# ardumsx.net
KiCad netlist of a schematic drawn in EAGLE
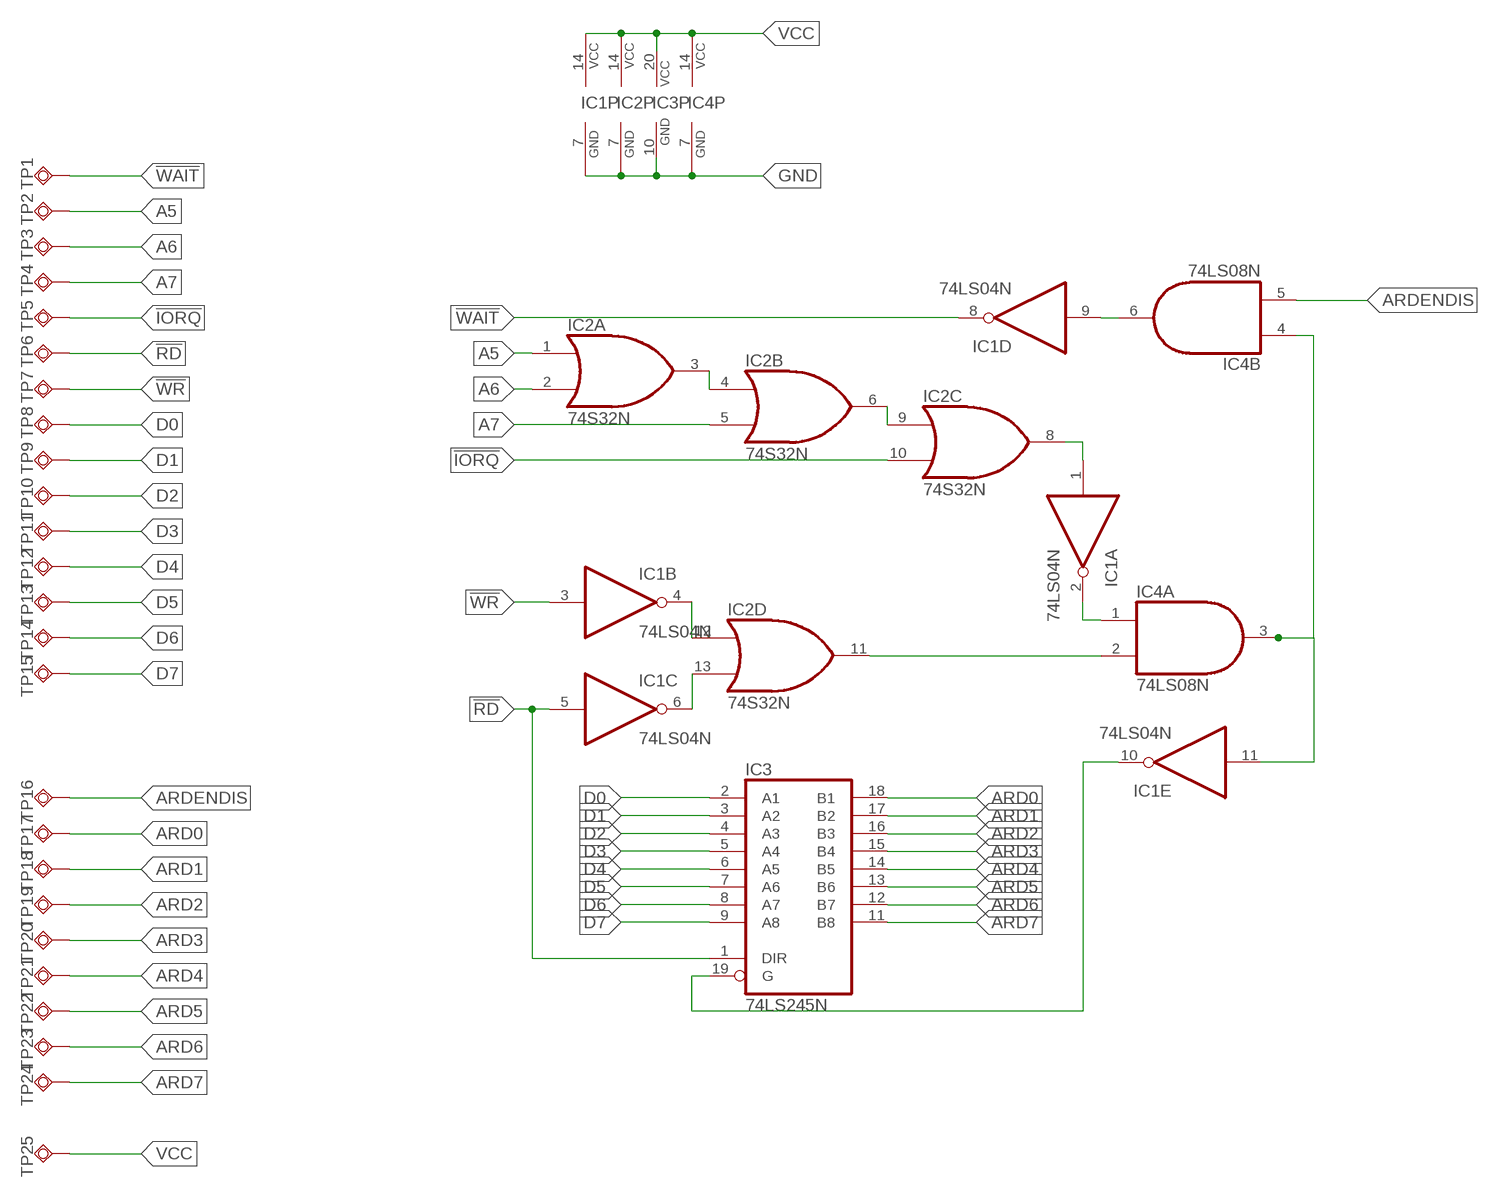
[diagram p0: schematic, sheet 1]

(export (version "E")
  (design (tool "Eeschema 10.0.6"))
  (components
    (comp (ref "IC1")
      (value "74LS04N")
      (footprint "eagle-import:DIL14")
      (libsource (lib "eagle-import") (part "7404NLS"))
    )
    (comp (ref "IC2")
      (value "74S32N")
      (footprint "eagle-import:DIL14")
      (libsource (lib "eagle-import") (part "7432NS"))
    )
    (comp (ref "IC3")
      (value "74LS245N")
      (footprint "eagle-import:DIL20")
      (libsource (lib "eagle-import") (part "74245NLS"))
    )
    (comp (ref "IC4")
      (value "74LS08N")
      (footprint "eagle-import:DIL14")
      (libsource (lib "eagle-import") (part "7408NLS"))
    )
    (comp (ref "TP1")
      (value "TPSQTP17R")
      (footprint "eagle-import:TP17R")
      (libsource (lib "eagle-import") (part "TPSQTP17R"))
    )
    (comp (ref "TP2")
      (value "TPSQTP17R")
      (footprint "eagle-import:TP17R")
      (libsource (lib "eagle-import") (part "TPSQTP17R"))
    )
    (comp (ref "TP3")
      (value "TPSQTP17R")
      (footprint "eagle-import:TP17R")
      (libsource (lib "eagle-import") (part "TPSQTP17R"))
    )
    (comp (ref "TP4")
      (value "TPSQTP17R")
      (footprint "eagle-import:TP17R")
      (libsource (lib "eagle-import") (part "TPSQTP17R"))
    )
    (comp (ref "TP5")
      (value "TPSQTP17R")
      (footprint "eagle-import:TP17R")
      (libsource (lib "eagle-import") (part "TPSQTP17R"))
    )
    (comp (ref "TP6")
      (value "TPSQTP17R")
      (footprint "eagle-import:TP17R")
      (libsource (lib "eagle-import") (part "TPSQTP17R"))
    )
    (comp (ref "TP7")
      (value "TPSQTP17R")
      (footprint "eagle-import:TP17R")
      (libsource (lib "eagle-import") (part "TPSQTP17R"))
    )
    (comp (ref "TP8")
      (value "TPSQTP17R")
      (footprint "eagle-import:TP17R")
      (libsource (lib "eagle-import") (part "TPSQTP17R"))
    )
    (comp (ref "TP9")
      (value "TPSQTP17R")
      (footprint "eagle-import:TP17R")
      (libsource (lib "eagle-import") (part "TPSQTP17R"))
    )
    (comp (ref "TP10")
      (value "TPSQTP17R")
      (footprint "eagle-import:TP17R")
      (libsource (lib "eagle-import") (part "TPSQTP17R"))
    )
    (comp (ref "TP11")
      (value "TPSQTP17R")
      (footprint "eagle-import:TP17R")
      (libsource (lib "eagle-import") (part "TPSQTP17R"))
    )
    (comp (ref "TP12")
      (value "TPSQTP17R")
      (footprint "eagle-import:TP17R")
      (libsource (lib "eagle-import") (part "TPSQTP17R"))
    )
    (comp (ref "TP13")
      (value "TPSQTP17R")
      (footprint "eagle-import:TP17R")
      (libsource (lib "eagle-import") (part "TPSQTP17R"))
    )
    (comp (ref "TP14")
      (value "TPSQTP17R")
      (footprint "eagle-import:TP17R")
      (libsource (lib "eagle-import") (part "TPSQTP17R"))
    )
    (comp (ref "TP15")
      (value "TPSQTP17R")
      (footprint "eagle-import:TP17R")
      (libsource (lib "eagle-import") (part "TPSQTP17R"))
    )
    (comp (ref "TP16")
      (value "TPSQTP17R")
      (footprint "eagle-import:TP17R")
      (libsource (lib "eagle-import") (part "TPSQTP17R"))
    )
    (comp (ref "TP17")
      (value "TPSQTP17R")
      (footprint "eagle-import:TP17R")
      (libsource (lib "eagle-import") (part "TPSQTP17R"))
    )
    (comp (ref "TP18")
      (value "TPSQTP17R")
      (footprint "eagle-import:TP17R")
      (libsource (lib "eagle-import") (part "TPSQTP17R"))
    )
    (comp (ref "TP19")
      (value "TPSQTP17R")
      (footprint "eagle-import:TP17R")
      (libsource (lib "eagle-import") (part "TPSQTP17R"))
    )
    (comp (ref "TP20")
      (value "TPSQTP17R")
      (footprint "eagle-import:TP17R")
      (libsource (lib "eagle-import") (part "TPSQTP17R"))
    )
    (comp (ref "TP21")
      (value "TPSQTP17R")
      (footprint "eagle-import:TP17R")
      (libsource (lib "eagle-import") (part "TPSQTP17R"))
    )
    (comp (ref "TP22")
      (value "TPSQTP17R")
      (footprint "eagle-import:TP17R")
      (libsource (lib "eagle-import") (part "TPSQTP17R"))
    )
    (comp (ref "TP23")
      (value "TPSQTP17R")
      (footprint "eagle-import:TP17R")
      (libsource (lib "eagle-import") (part "TPSQTP17R"))
    )
    (comp (ref "TP24")
      (value "TPSQTP17R")
      (footprint "eagle-import:TP17R")
      (libsource (lib "eagle-import") (part "TPSQTP17R"))
    )
    (comp (ref "TP25")
      (value "TPSQTP17R")
      (footprint "eagle-import:TP17R")
      (libsource (lib "eagle-import") (part "TPSQTP17R"))
    )
  )
  (nets
    (net (code "1") (name "/~{IORQ}") (class "Default")
      (node (ref "IC2") (pin "10") (pinfunction "I1_10") (pintype "input"))
      (node (ref "TP5") (pin "TP") (pinfunction "TP_TP") (pintype "input"))
    )
    (net (code "2") (name "/~{RD}") (class "Default")
      (node (ref "IC1") (pin "5") (pinfunction "I_5") (pintype "input"))
      (node (ref "IC3") (pin "1") (pinfunction "DIR_1") (pintype "input"))
      (node (ref "TP6") (pin "TP") (pinfunction "TP_TP") (pintype "input"))
    )
    (net (code "3") (name "/~{WAIT}") (class "Default")
      (node (ref "IC1") (pin "8") (pinfunction "O_8") (pintype "output"))
      (node (ref "TP1") (pin "TP") (pinfunction "TP_TP") (pintype "input"))
    )
    (net (code "4") (name "/~{WR}") (class "Default")
      (node (ref "IC1") (pin "3") (pinfunction "I_3") (pintype "input"))
      (node (ref "TP7") (pin "TP") (pinfunction "TP_TP") (pintype "input"))
    )
    (net (code "5") (name "A5") (class "Default")
      (node (ref "IC2") (pin "1") (pinfunction "I0_1") (pintype "input"))
      (node (ref "TP2") (pin "TP") (pinfunction "TP_TP") (pintype "input"))
    )
    (net (code "6") (name "A6") (class "Default")
      (node (ref "IC2") (pin "2") (pinfunction "I1_2") (pintype "input"))
      (node (ref "TP3") (pin "TP") (pinfunction "TP_TP") (pintype "input"))
    )
    (net (code "7") (name "A7") (class "Default")
      (node (ref "IC2") (pin "5") (pinfunction "I1_5") (pintype "input"))
      (node (ref "TP4") (pin "TP") (pinfunction "TP_TP") (pintype "input"))
    )
    (net (code "8") (name "ARD0") (class "Default")
      (node (ref "IC3") (pin "18") (pinfunction "B1_18") (pintype "bidirectional"))
      (node (ref "TP17") (pin "TP") (pinfunction "TP_TP") (pintype "input"))
    )
    (net (code "9") (name "ARD1") (class "Default")
      (node (ref "IC3") (pin "17") (pinfunction "B2_17") (pintype "bidirectional"))
      (node (ref "TP18") (pin "TP") (pinfunction "TP_TP") (pintype "input"))
    )
    (net (code "10") (name "ARD2") (class "Default")
      (node (ref "IC3") (pin "16") (pinfunction "B3_16") (pintype "bidirectional"))
      (node (ref "TP19") (pin "TP") (pinfunction "TP_TP") (pintype "input"))
    )
    (net (code "11") (name "ARD3") (class "Default")
      (node (ref "IC3") (pin "15") (pinfunction "B4_15") (pintype "bidirectional"))
      (node (ref "TP20") (pin "TP") (pinfunction "TP_TP") (pintype "input"))
    )
    (net (code "12") (name "ARD4") (class "Default")
      (node (ref "IC3") (pin "14") (pinfunction "B5_14") (pintype "bidirectional"))
      (node (ref "TP21") (pin "TP") (pinfunction "TP_TP") (pintype "input"))
    )
    (net (code "13") (name "ARD5") (class "Default")
      (node (ref "IC3") (pin "13") (pinfunction "B6_13") (pintype "bidirectional"))
      (node (ref "TP22") (pin "TP") (pinfunction "TP_TP") (pintype "input"))
    )
    (net (code "14") (name "ARD6") (class "Default")
      (node (ref "IC3") (pin "12") (pinfunction "B7_12") (pintype "bidirectional"))
      (node (ref "TP23") (pin "TP") (pinfunction "TP_TP") (pintype "input"))
    )
    (net (code "15") (name "ARD7") (class "Default")
      (node (ref "IC3") (pin "11") (pinfunction "B8_11") (pintype "bidirectional"))
      (node (ref "TP24") (pin "TP") (pinfunction "TP_TP") (pintype "input"))
    )
    (net (code "16") (name "ARDENDIS") (class "Default")
      (node (ref "IC4") (pin "5") (pinfunction "I1_5") (pintype "input"))
      (node (ref "TP16") (pin "TP") (pinfunction "TP_TP") (pintype "input"))
    )
    (net (code "17") (name "D0") (class "Default")
      (node (ref "IC3") (pin "2") (pinfunction "A1_2") (pintype "bidirectional"))
      (node (ref "TP8") (pin "TP") (pinfunction "TP_TP") (pintype "input"))
    )
    (net (code "18") (name "D1") (class "Default")
      (node (ref "IC3") (pin "3") (pinfunction "A2_3") (pintype "bidirectional"))
      (node (ref "TP9") (pin "TP") (pinfunction "TP_TP") (pintype "input"))
    )
    (net (code "19") (name "D2") (class "Default")
      (node (ref "IC3") (pin "4") (pinfunction "A3_4") (pintype "bidirectional"))
      (node (ref "TP10") (pin "TP") (pinfunction "TP_TP") (pintype "input"))
    )
    (net (code "20") (name "D3") (class "Default")
      (node (ref "IC3") (pin "5") (pinfunction "A4_5") (pintype "bidirectional"))
      (node (ref "TP11") (pin "TP") (pinfunction "TP_TP") (pintype "input"))
    )
    (net (code "21") (name "D4") (class "Default")
      (node (ref "IC3") (pin "6") (pinfunction "A5_6") (pintype "bidirectional"))
      (node (ref "TP12") (pin "TP") (pinfunction "TP_TP") (pintype "input"))
    )
    (net (code "22") (name "D5") (class "Default")
      (node (ref "IC3") (pin "7") (pinfunction "A6_7") (pintype "bidirectional"))
      (node (ref "TP13") (pin "TP") (pinfunction "TP_TP") (pintype "input"))
    )
    (net (code "23") (name "D6") (class "Default")
      (node (ref "IC3") (pin "8") (pinfunction "A7_8") (pintype "bidirectional"))
      (node (ref "TP14") (pin "TP") (pinfunction "TP_TP") (pintype "input"))
    )
    (net (code "24") (name "D7") (class "Default")
      (node (ref "IC3") (pin "9") (pinfunction "A8_9") (pintype "bidirectional"))
      (node (ref "TP15") (pin "TP") (pinfunction "TP_TP") (pintype "input"))
    )
    (net (code "25") (name "GND") (class "Default")
      (node (ref "IC1") (pin "7") (pinfunction "GND_7") (pintype "power_in"))
      (node (ref "IC2") (pin "7") (pinfunction "GND_7") (pintype "power_in"))
      (node (ref "IC3") (pin "10") (pinfunction "GND_10") (pintype "power_in"))
      (node (ref "IC4") (pin "7") (pinfunction "GND_7") (pintype "power_in"))
    )
    (net (code "26") (name "Net-(IC1A-I)") (class "Default")
      (node (ref "IC1") (pin "1") (pinfunction "I_1") (pintype "input"))
      (node (ref "IC2") (pin "8") (pinfunction "O_8") (pintype "output"))
    )
    (net (code "27") (name "Net-(IC1A-O)") (class "Default")
      (node (ref "IC1") (pin "2") (pinfunction "O_2") (pintype "output"))
      (node (ref "IC4") (pin "1") (pinfunction "I0_1") (pintype "input"))
    )
    (net (code "28") (name "Net-(IC1B-O)") (class "Default")
      (node (ref "IC1") (pin "4") (pinfunction "O_4") (pintype "output"))
      (node (ref "IC2") (pin "12") (pinfunction "I0_12") (pintype "input"))
    )
    (net (code "29") (name "Net-(IC1C-O)") (class "Default")
      (node (ref "IC1") (pin "6") (pinfunction "O_6") (pintype "output"))
      (node (ref "IC2") (pin "13") (pinfunction "I1_13") (pintype "input"))
    )
    (net (code "30") (name "Net-(IC1D-I)") (class "Default")
      (node (ref "IC1") (pin "9") (pinfunction "I_9") (pintype "input"))
      (node (ref "IC4") (pin "6") (pinfunction "O_6") (pintype "output"))
    )
    (net (code "31") (name "Net-(IC1E-I)") (class "Default")
      (node (ref "IC1") (pin "11") (pinfunction "I_11") (pintype "input"))
      (node (ref "IC4") (pin "3") (pinfunction "O_3") (pintype "output"))
      (node (ref "IC4") (pin "4") (pinfunction "I0_4") (pintype "input"))
    )
    (net (code "32") (name "Net-(IC1E-O)") (class "Default")
      (node (ref "IC1") (pin "10") (pinfunction "O_10") (pintype "output"))
      (node (ref "IC3") (pin "19") (pinfunction "G_19") (pintype "input"))
    )
    (net (code "33") (name "Net-(IC2A-O)") (class "Default")
      (node (ref "IC2") (pin "3") (pinfunction "O_3") (pintype "output"))
      (node (ref "IC2") (pin "4") (pinfunction "I0_4") (pintype "input"))
    )
    (net (code "34") (name "Net-(IC2B-O)") (class "Default")
      (node (ref "IC2") (pin "6") (pinfunction "O_6") (pintype "output"))
      (node (ref "IC2") (pin "9") (pinfunction "I0_9") (pintype "input"))
    )
    (net (code "35") (name "Net-(IC2D-O)") (class "Default")
      (node (ref "IC2") (pin "11") (pinfunction "O_11") (pintype "output"))
      (node (ref "IC4") (pin "2") (pinfunction "I1_2") (pintype "input"))
    )
    (net (code "36") (name "VCC") (class "Default")
      (node (ref "IC1") (pin "14") (pinfunction "VCC_14") (pintype "power_in"))
      (node (ref "IC2") (pin "14") (pinfunction "VCC_14") (pintype "power_in"))
      (node (ref "IC3") (pin "20") (pinfunction "VCC_20") (pintype "power_in"))
      (node (ref "IC4") (pin "14") (pinfunction "VCC_14") (pintype "power_in"))
      (node (ref "TP25") (pin "TP") (pinfunction "TP_TP") (pintype "input"))
    )
  )
)
